# Segger_JTAG_v1p3.net
KiCad netlist of a schematic drawn in EAGLE
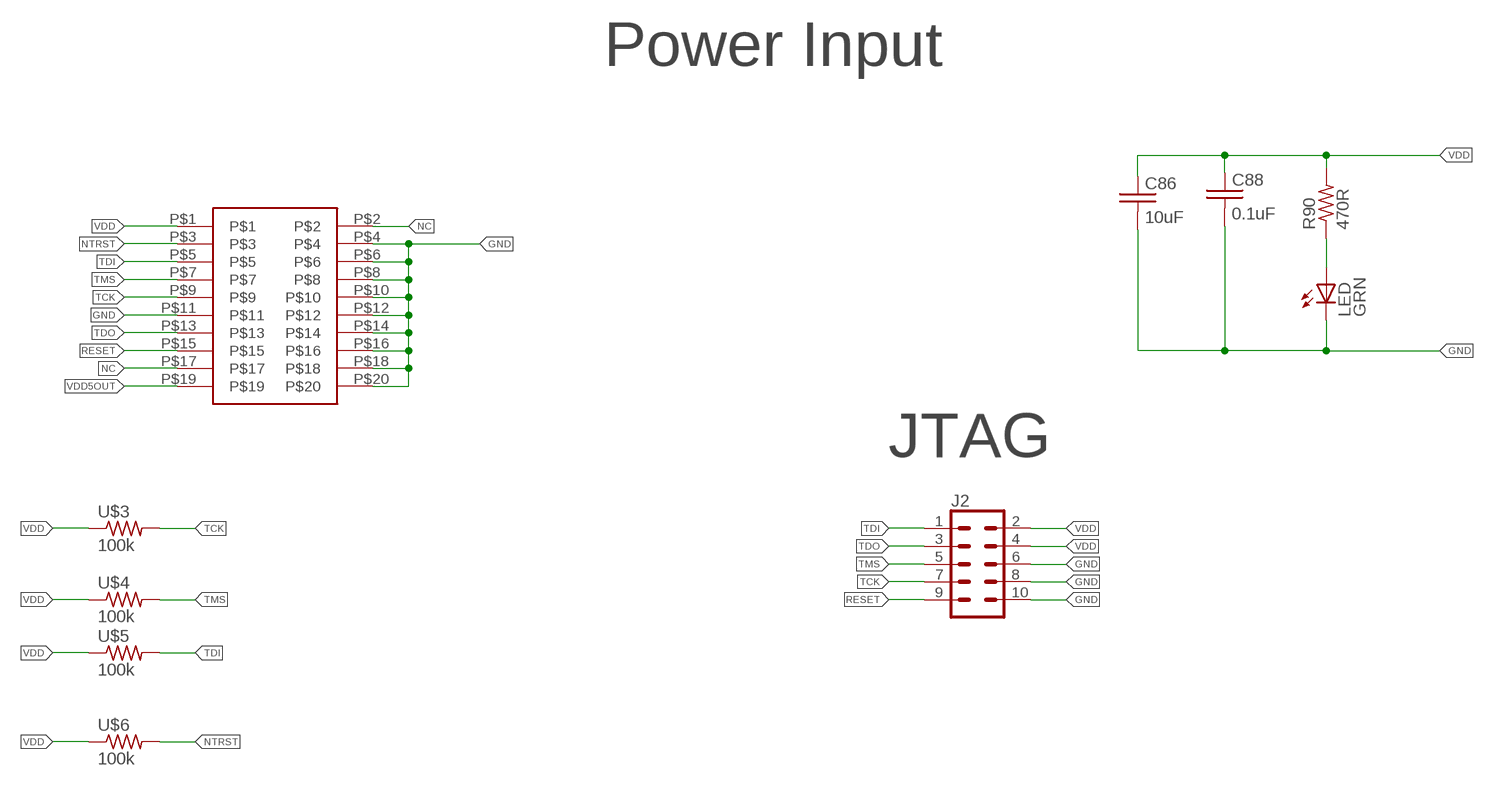
[diagram p0: schematic, sheet 1]

(export (version "E")
  (design (tool "Eeschema 10.0.6"))
  (components
    (comp (ref "C86")
      (value "10uF")
      (footprint "eagle-import:0805")
      (libsource (lib "eagle-import") (part "C_0805"))
    )
    (comp (ref "C88")
      (value "0.1uF")
      (footprint "eagle-import:0805")
      (libsource (lib "eagle-import") (part "C_0805"))
    )
    (comp (ref "J2")
      (value "CONN_05X2PTH")
      (footprint "eagle-import:2X5")
      (libsource (lib "eagle-import") (part "CONN_05X2PTH"))
    )
    (comp (ref "LED")
      (value "LED_0805_GREEN")
      (footprint "eagle-import:LED_0805_GREEN")
      (libsource (lib "eagle-import") (part "LED_0805_GREEN"))
    )
    (comp (ref "R90")
      (value "470R")
      (footprint "eagle-import:0805")
      (libsource (lib "eagle-import") (part "R_0805"))
    )
    (comp (ref "U$2")
      (value "2_X_10_HEADER_GENERIC")
      (footprint "eagle-import:2_X_10_.1_INCH")
      (libsource (lib "eagle-import") (part "2_X_10_HEADER_GENERIC"))
    )
    (comp (ref "U$3")
      (value "100k")
      (footprint "eagle-import:0805")
      (libsource (lib "eagle-import") (part "R_0805"))
    )
    (comp (ref "U$4")
      (value "100k")
      (footprint "eagle-import:0805")
      (libsource (lib "eagle-import") (part "R_0805"))
    )
    (comp (ref "U$5")
      (value "100k")
      (footprint "eagle-import:0805")
      (libsource (lib "eagle-import") (part "R_0805"))
    )
    (comp (ref "U$6")
      (value "100k")
      (footprint "eagle-import:0805")
      (libsource (lib "eagle-import") (part "R_0805"))
    )
  )
  (nets
    (net (code "1") (name "GND") (class "Default")
      (node (ref "C86") (pin "2") (pinfunction "2_2") (pintype "passive"))
      (node (ref "C88") (pin "2") (pinfunction "2_2") (pintype "passive"))
      (node (ref "J2") (pin "10") (pinfunction "10_10") (pintype "passive"))
      (node (ref "J2") (pin "6") (pinfunction "6_6") (pintype "passive"))
      (node (ref "J2") (pin "8") (pinfunction "8_8") (pintype "passive"))
      (node (ref "LED") (pin "C") (pinfunction "C_C") (pintype "passive"))
      (node (ref "U$2") (pin "P$10") (pinfunction "P$10_P$10") (pintype "bidirectional"))
      (node (ref "U$2") (pin "P$11") (pinfunction "P$11_P$11") (pintype "bidirectional"))
      (node (ref "U$2") (pin "P$12") (pinfunction "P$12_P$12") (pintype "bidirectional"))
      (node (ref "U$2") (pin "P$14") (pinfunction "P$14_P$14") (pintype "bidirectional"))
      (node (ref "U$2") (pin "P$16") (pinfunction "P$16_P$16") (pintype "bidirectional"))
      (node (ref "U$2") (pin "P$18") (pinfunction "P$18_P$18") (pintype "bidirectional"))
      (node (ref "U$2") (pin "P$20") (pinfunction "P$20_P$20") (pintype "bidirectional"))
      (node (ref "U$2") (pin "P$4") (pinfunction "P$4_P$4") (pintype "bidirectional"))
      (node (ref "U$2") (pin "P$6") (pinfunction "P$6_P$6") (pintype "bidirectional"))
      (node (ref "U$2") (pin "P$8") (pinfunction "P$8_P$8") (pintype "bidirectional"))
    )
    (net (code "2") (name "NC") (class "Default")
      (node (ref "U$2") (pin "P$17") (pinfunction "P$17_P$17") (pintype "bidirectional"))
      (node (ref "U$2") (pin "P$2") (pinfunction "P$2_P$2") (pintype "bidirectional"))
    )
    (net (code "3") (name "NTRST") (class "Default")
      (node (ref "U$2") (pin "P$3") (pinfunction "P$3_P$3") (pintype "bidirectional"))
      (node (ref "U$6") (pin "2") (pinfunction "2_2") (pintype "passive"))
    )
    (net (code "4") (name "Net-(LED-PadA)") (class "Default")
      (node (ref "LED") (pin "A") (pinfunction "A_A") (pintype "passive"))
      (node (ref "R90") (pin "1") (pinfunction "1_1") (pintype "passive"))
    )
    (net (code "5") (name "RESET") (class "Default")
      (node (ref "J2") (pin "9") (pinfunction "9_9") (pintype "passive"))
      (node (ref "U$2") (pin "P$15") (pinfunction "P$15_P$15") (pintype "bidirectional"))
    )
    (net (code "6") (name "TCK") (class "Default")
      (node (ref "J2") (pin "7") (pinfunction "7_7") (pintype "passive"))
      (node (ref "U$2") (pin "P$9") (pinfunction "P$9_P$9") (pintype "bidirectional"))
      (node (ref "U$3") (pin "2") (pinfunction "2_2") (pintype "passive"))
    )
    (net (code "7") (name "TDI") (class "Default")
      (node (ref "J2") (pin "1") (pinfunction "1_1") (pintype "passive"))
      (node (ref "U$2") (pin "P$5") (pinfunction "P$5_P$5") (pintype "bidirectional"))
      (node (ref "U$5") (pin "2") (pinfunction "2_2") (pintype "passive"))
    )
    (net (code "8") (name "TDO") (class "Default")
      (node (ref "J2") (pin "3") (pinfunction "3_3") (pintype "passive"))
      (node (ref "U$2") (pin "P$13") (pinfunction "P$13_P$13") (pintype "bidirectional"))
    )
    (net (code "9") (name "TMS") (class "Default")
      (node (ref "J2") (pin "5") (pinfunction "5_5") (pintype "passive"))
      (node (ref "U$2") (pin "P$7") (pinfunction "P$7_P$7") (pintype "bidirectional"))
      (node (ref "U$4") (pin "2") (pinfunction "2_2") (pintype "passive"))
    )
    (net (code "10") (name "VDD") (class "Default")
      (node (ref "C86") (pin "1") (pinfunction "1_1") (pintype "passive"))
      (node (ref "C88") (pin "1") (pinfunction "1_1") (pintype "passive"))
      (node (ref "J2") (pin "2") (pinfunction "2_2") (pintype "passive"))
      (node (ref "J2") (pin "4") (pinfunction "4_4") (pintype "passive"))
      (node (ref "R90") (pin "2") (pinfunction "2_2") (pintype "passive"))
      (node (ref "U$2") (pin "P$1") (pinfunction "P$1_P$1") (pintype "bidirectional"))
      (node (ref "U$3") (pin "1") (pinfunction "1_1") (pintype "passive"))
      (node (ref "U$4") (pin "1") (pinfunction "1_1") (pintype "passive"))
      (node (ref "U$5") (pin "1") (pinfunction "1_1") (pintype "passive"))
      (node (ref "U$6") (pin "1") (pinfunction "1_1") (pintype "passive"))
    )
    (net (code "11") (name "VDD5OUT") (class "Default")
      (node (ref "U$2") (pin "P$19") (pinfunction "P$19_P$19") (pintype "bidirectional"))
    )
  )
)
